# dualHbridge.net
KiCad netlist of a schematic drawn in EAGLE
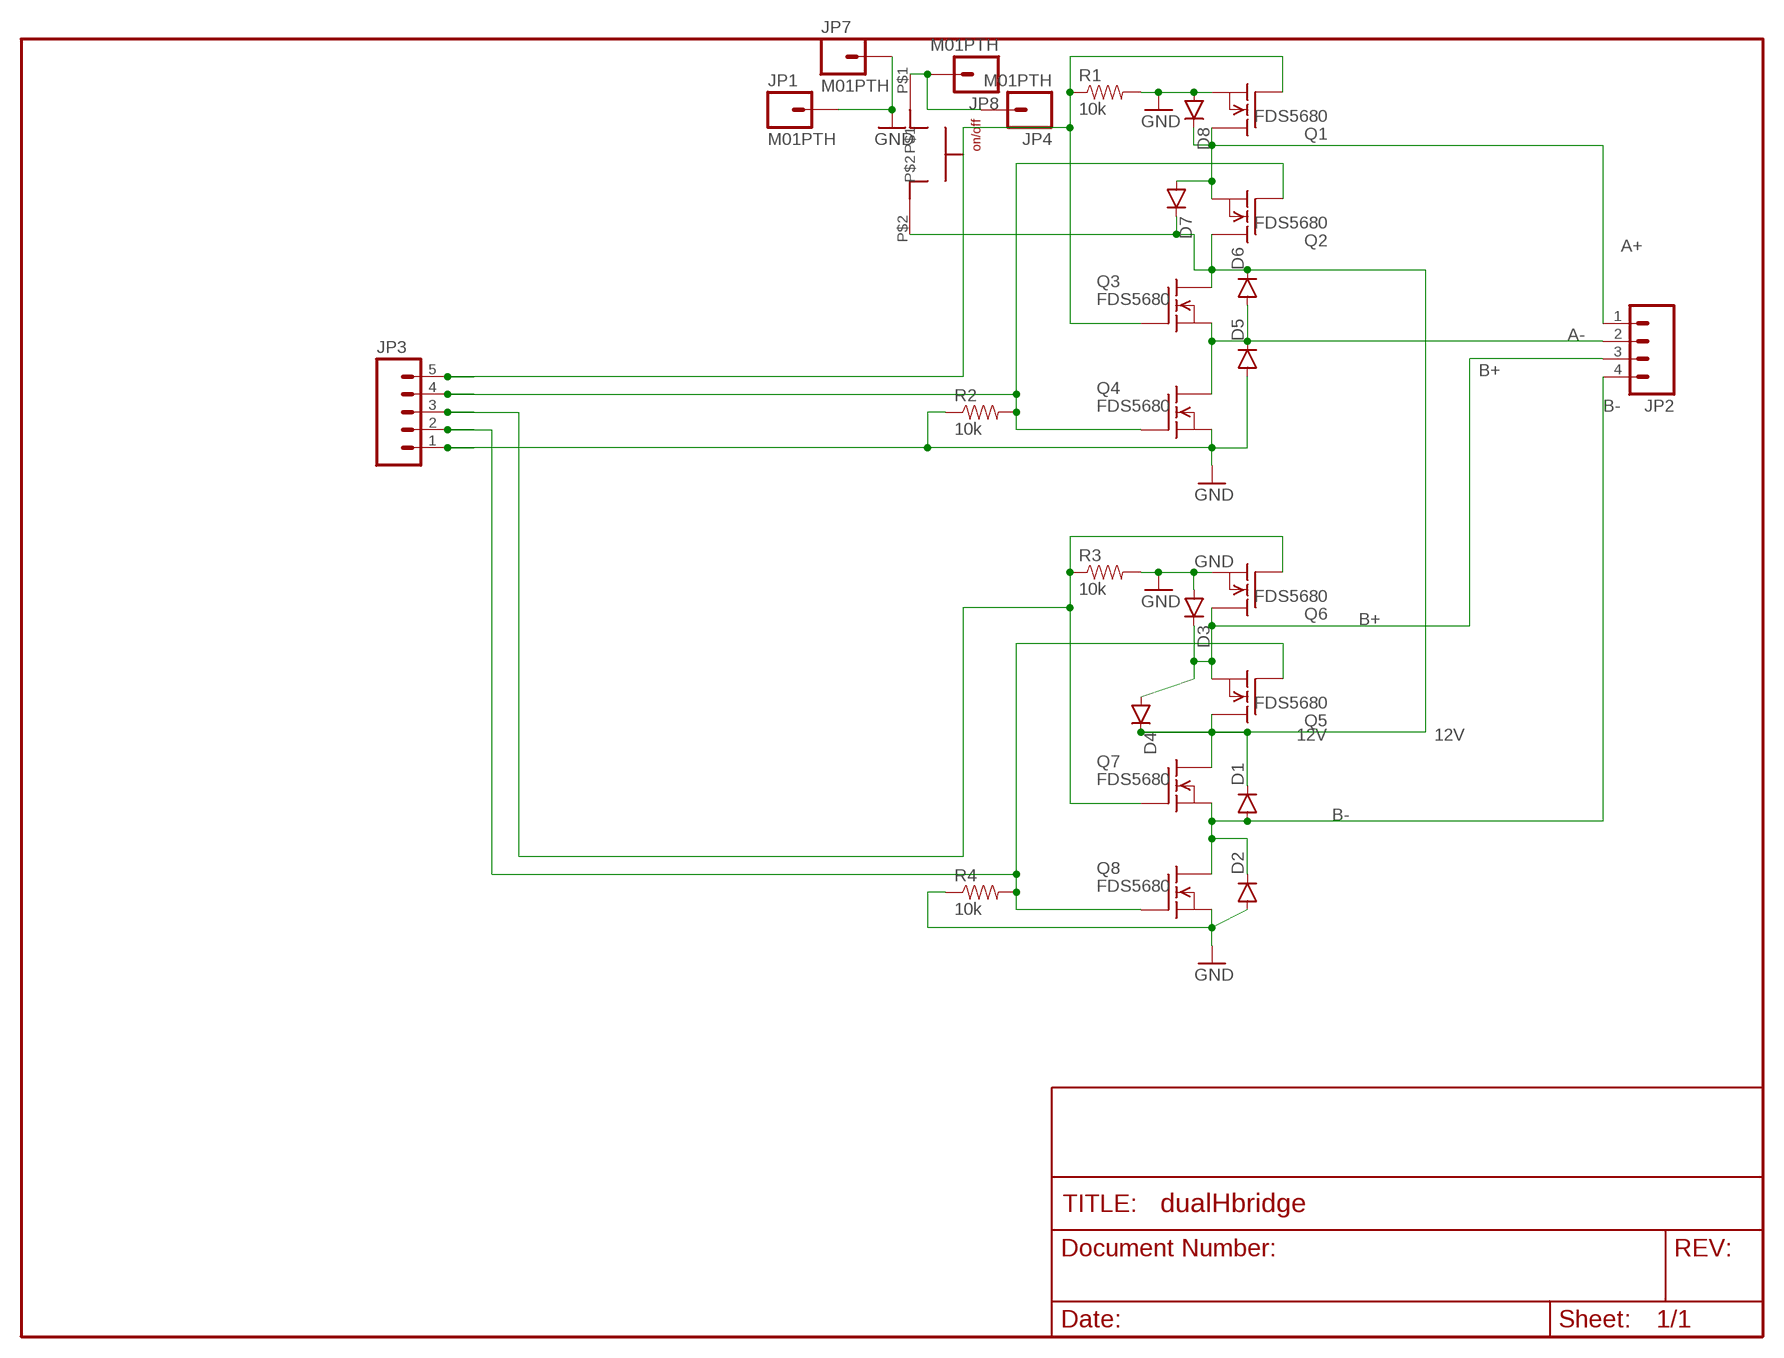
[diagram p0: schematic, sheet 1]

(export (version "E")
  (design (tool "Eeschema 10.0.6"))
  (components
    (comp (ref "D1")
      (value "DIODEKIT2")
      (footprint "eagle-import:DIODE-1N4001-KIT")
      (libsource (lib "eagle-import") (part "DIODEKIT2"))
    )
    (comp (ref "D2")
      (value "DIODEKIT2")
      (footprint "eagle-import:DIODE-1N4001-KIT")
      (libsource (lib "eagle-import") (part "DIODEKIT2"))
    )
    (comp (ref "D3")
      (value "DIODEKIT2")
      (footprint "eagle-import:DIODE-1N4001-KIT")
      (libsource (lib "eagle-import") (part "DIODEKIT2"))
    )
    (comp (ref "D4")
      (value "DIODEKIT2")
      (footprint "eagle-import:DIODE-1N4001-KIT")
      (libsource (lib "eagle-import") (part "DIODEKIT2"))
    )
    (comp (ref "D5")
      (value "DIODEKIT2")
      (footprint "eagle-import:DIODE-1N4001-KIT")
      (libsource (lib "eagle-import") (part "DIODEKIT2"))
    )
    (comp (ref "D6")
      (value "DIODEKIT2")
      (footprint "eagle-import:DIODE-1N4001-KIT")
      (libsource (lib "eagle-import") (part "DIODEKIT2"))
    )
    (comp (ref "D7")
      (value "DIODEKIT2")
      (footprint "eagle-import:DIODE-1N4001-KIT")
      (libsource (lib "eagle-import") (part "DIODEKIT2"))
    )
    (comp (ref "D8")
      (value "DIODEKIT2")
      (footprint "eagle-import:DIODE-1N4001-KIT")
      (libsource (lib "eagle-import") (part "DIODEKIT2"))
    )
    (comp (ref "JP1")
      (value "M01PTH")
      (footprint "eagle-import:1X01")
      (libsource (lib "eagle-import") (part "M01PTH"))
    )
    (comp (ref "JP2")
      (value "M04LONGPADS")
      (footprint "eagle-import:1X04_LONGPADS")
      (libsource (lib "eagle-import") (part "M04LONGPADS"))
    )
    (comp (ref "JP3")
      (value "M05PTH")
      (footprint "eagle-import:1X05")
      (libsource (lib "eagle-import") (part "M05PTH"))
    )
    (comp (ref "JP4")
      (value "M01PTH")
      (footprint "eagle-import:1X01")
      (libsource (lib "eagle-import") (part "M01PTH"))
    )
    (comp (ref "JP7")
      (value "M01PTH")
      (footprint "eagle-import:1X01")
      (libsource (lib "eagle-import") (part "M01PTH"))
    )
    (comp (ref "JP8")
      (value "M01PTH")
      (footprint "eagle-import:1X01")
      (libsource (lib "eagle-import") (part "M01PTH"))
    )
    (comp (ref "Q1")
      (value "FDS5680")
      (footprint "eagle-import:SO-8")
      (libsource (lib "eagle-import") (part "FDS5680"))
    )
    (comp (ref "Q2")
      (value "FDS5680")
      (footprint "eagle-import:SO-8")
      (libsource (lib "eagle-import") (part "FDS5680"))
    )
    (comp (ref "Q3")
      (value "FDS5680")
      (footprint "eagle-import:SO-8")
      (libsource (lib "eagle-import") (part "FDS5680"))
    )
    (comp (ref "Q4")
      (value "FDS5680")
      (footprint "eagle-import:SO-8")
      (libsource (lib "eagle-import") (part "FDS5680"))
    )
    (comp (ref "Q5")
      (value "FDS5680")
      (footprint "eagle-import:SO-8")
      (libsource (lib "eagle-import") (part "FDS5680"))
    )
    (comp (ref "Q6")
      (value "FDS5680")
      (footprint "eagle-import:SO-8")
      (libsource (lib "eagle-import") (part "FDS5680"))
    )
    (comp (ref "Q7")
      (value "FDS5680")
      (footprint "eagle-import:SO-8")
      (libsource (lib "eagle-import") (part "FDS5680"))
    )
    (comp (ref "Q8")
      (value "FDS5680")
      (footprint "eagle-import:SO-8")
      (libsource (lib "eagle-import") (part "FDS5680"))
    )
    (comp (ref "R1")
      (value "10k")
      (footprint "eagle-import:0603-RES")
      (libsource (lib "eagle-import") (part "RESISTOR0603-RES"))
    )
    (comp (ref "R2")
      (value "10k")
      (footprint "eagle-import:0603-RES")
      (libsource (lib "eagle-import") (part "RESISTOR0603-RES"))
    )
    (comp (ref "R3")
      (value "10k")
      (footprint "eagle-import:0603-RES")
      (libsource (lib "eagle-import") (part "RESISTOR0603-RES"))
    )
    (comp (ref "R4")
      (value "10k")
      (footprint "eagle-import:0603-RES")
      (libsource (lib "eagle-import") (part "RESISTOR0603-RES"))
    )
    (comp (ref "U$5")
      (value "CW182-ND")
      (footprint "eagle-import:CW182-ND")
      (libsource (lib "eagle-import") (part "CW182-ND"))
    )
  )
  (nets
    (net (code "1") (name "/12V") (class "Default")
      (node (ref "D1") (pin "C") (pinfunction "C_C") (pintype "passive"))
      (node (ref "D4") (pin "C") (pinfunction "C_C") (pintype "passive"))
      (node (ref "D6") (pin "C") (pinfunction "C_C") (pintype "passive"))
      (node (ref "D7") (pin "C") (pinfunction "C_C") (pintype "passive"))
      (node (ref "Q2") (pin "5") (pinfunction "D_5") (pintype "passive"))
      (node (ref "Q2") (pin "6") (pinfunction "D_6") (pintype "passive"))
      (node (ref "Q2") (pin "7") (pinfunction "D_7") (pintype "passive"))
      (node (ref "Q2") (pin "8") (pinfunction "D_8") (pintype "passive"))
      (node (ref "Q3") (pin "5") (pinfunction "D_5") (pintype "passive"))
      (node (ref "Q3") (pin "6") (pinfunction "D_6") (pintype "passive"))
      (node (ref "Q3") (pin "7") (pinfunction "D_7") (pintype "passive"))
      (node (ref "Q3") (pin "8") (pinfunction "D_8") (pintype "passive"))
      (node (ref "Q5") (pin "5") (pinfunction "D_5") (pintype "passive"))
      (node (ref "Q5") (pin "6") (pinfunction "D_6") (pintype "passive"))
      (node (ref "Q5") (pin "7") (pinfunction "D_7") (pintype "passive"))
      (node (ref "Q5") (pin "8") (pinfunction "D_8") (pintype "passive"))
      (node (ref "Q7") (pin "5") (pinfunction "D_5") (pintype "passive"))
      (node (ref "Q7") (pin "6") (pinfunction "D_6") (pintype "passive"))
      (node (ref "Q7") (pin "7") (pinfunction "D_7") (pintype "passive"))
      (node (ref "Q7") (pin "8") (pinfunction "D_8") (pintype "passive"))
      (node (ref "U$5") (pin "P$2") (pinfunction "P$2_P$2") (pintype "bidirectional"))
    )
    (net (code "2") (name "/A+") (class "Default")
      (node (ref "D7") (pin "A") (pinfunction "A_A") (pintype "passive"))
      (node (ref "D8") (pin "C") (pinfunction "C_C") (pintype "passive"))
      (node (ref "JP2") (pin "1") (pinfunction "1_1") (pintype "passive"))
      (node (ref "Q1") (pin "5") (pinfunction "D_5") (pintype "passive"))
      (node (ref "Q1") (pin "6") (pinfunction "D_6") (pintype "passive"))
      (node (ref "Q1") (pin "7") (pinfunction "D_7") (pintype "passive"))
      (node (ref "Q1") (pin "8") (pinfunction "D_8") (pintype "passive"))
      (node (ref "Q2") (pin "1") (pinfunction "S_1") (pintype "passive"))
      (node (ref "Q2") (pin "2") (pinfunction "S_2") (pintype "passive"))
      (node (ref "Q2") (pin "3") (pinfunction "S_3") (pintype "passive"))
    )
    (net (code "3") (name "/A-") (class "Default")
      (node (ref "D5") (pin "C") (pinfunction "C_C") (pintype "passive"))
      (node (ref "D6") (pin "A") (pinfunction "A_A") (pintype "passive"))
      (node (ref "JP2") (pin "2") (pinfunction "2_2") (pintype "passive"))
      (node (ref "Q3") (pin "1") (pinfunction "S_1") (pintype "passive"))
      (node (ref "Q3") (pin "2") (pinfunction "S_2") (pintype "passive"))
      (node (ref "Q3") (pin "3") (pinfunction "S_3") (pintype "passive"))
      (node (ref "Q4") (pin "5") (pinfunction "D_5") (pintype "passive"))
      (node (ref "Q4") (pin "6") (pinfunction "D_6") (pintype "passive"))
      (node (ref "Q4") (pin "7") (pinfunction "D_7") (pintype "passive"))
      (node (ref "Q4") (pin "8") (pinfunction "D_8") (pintype "passive"))
    )
    (net (code "4") (name "/B+") (class "Default")
      (node (ref "D3") (pin "C") (pinfunction "C_C") (pintype "passive"))
      (node (ref "D4") (pin "A") (pinfunction "A_A") (pintype "passive"))
      (node (ref "JP2") (pin "3") (pinfunction "3_3") (pintype "passive"))
      (node (ref "Q5") (pin "1") (pinfunction "S_1") (pintype "passive"))
      (node (ref "Q5") (pin "2") (pinfunction "S_2") (pintype "passive"))
      (node (ref "Q5") (pin "3") (pinfunction "S_3") (pintype "passive"))
      (node (ref "Q6") (pin "5") (pinfunction "D_5") (pintype "passive"))
      (node (ref "Q6") (pin "6") (pinfunction "D_6") (pintype "passive"))
      (node (ref "Q6") (pin "7") (pinfunction "D_7") (pintype "passive"))
      (node (ref "Q6") (pin "8") (pinfunction "D_8") (pintype "passive"))
    )
    (net (code "5") (name "/B-") (class "Default")
      (node (ref "D1") (pin "A") (pinfunction "A_A") (pintype "passive"))
      (node (ref "D2") (pin "C") (pinfunction "C_C") (pintype "passive"))
      (node (ref "JP2") (pin "4") (pinfunction "4_4") (pintype "passive"))
      (node (ref "Q7") (pin "1") (pinfunction "S_1") (pintype "passive"))
      (node (ref "Q7") (pin "2") (pinfunction "S_2") (pintype "passive"))
      (node (ref "Q7") (pin "3") (pinfunction "S_3") (pintype "passive"))
      (node (ref "Q8") (pin "5") (pinfunction "D_5") (pintype "passive"))
      (node (ref "Q8") (pin "6") (pinfunction "D_6") (pintype "passive"))
      (node (ref "Q8") (pin "7") (pinfunction "D_7") (pintype "passive"))
      (node (ref "Q8") (pin "8") (pinfunction "D_8") (pintype "passive"))
    )
    (net (code "6") (name "GND") (class "Default")
      (node (ref "D2") (pin "A") (pinfunction "A_A") (pintype "passive"))
      (node (ref "D3") (pin "A") (pinfunction "A_A") (pintype "passive"))
      (node (ref "D5") (pin "A") (pinfunction "A_A") (pintype "passive"))
      (node (ref "D8") (pin "A") (pinfunction "A_A") (pintype "passive"))
      (node (ref "JP1") (pin "1") (pinfunction "1_1") (pintype "passive"))
      (node (ref "JP3") (pin "1") (pinfunction "1_1") (pintype "passive"))
      (node (ref "JP7") (pin "1") (pinfunction "1_1") (pintype "passive"))
      (node (ref "Q1") (pin "1") (pinfunction "S_1") (pintype "passive"))
      (node (ref "Q1") (pin "2") (pinfunction "S_2") (pintype "passive"))
      (node (ref "Q1") (pin "3") (pinfunction "S_3") (pintype "passive"))
      (node (ref "Q4") (pin "1") (pinfunction "S_1") (pintype "passive"))
      (node (ref "Q4") (pin "2") (pinfunction "S_2") (pintype "passive"))
      (node (ref "Q4") (pin "3") (pinfunction "S_3") (pintype "passive"))
      (node (ref "Q6") (pin "1") (pinfunction "S_1") (pintype "passive"))
      (node (ref "Q6") (pin "2") (pinfunction "S_2") (pintype "passive"))
      (node (ref "Q6") (pin "3") (pinfunction "S_3") (pintype "passive"))
      (node (ref "Q8") (pin "1") (pinfunction "S_1") (pintype "passive"))
      (node (ref "Q8") (pin "2") (pinfunction "S_2") (pintype "passive"))
      (node (ref "Q8") (pin "3") (pinfunction "S_3") (pintype "passive"))
      (node (ref "R1") (pin "2") (pinfunction "2_2") (pintype "passive"))
      (node (ref "R2") (pin "1") (pinfunction "1_1") (pintype "passive"))
      (node (ref "R3") (pin "2") (pinfunction "2_2") (pintype "passive"))
      (node (ref "R4") (pin "1") (pinfunction "1_1") (pintype "passive"))
    )
    (net (code "7") (name "Net-(JP4-Pad1)") (class "Default")
      (node (ref "JP4") (pin "1") (pinfunction "1_1") (pintype "passive"))
      (node (ref "JP8") (pin "1") (pinfunction "1_1") (pintype "passive"))
      (node (ref "U$5") (pin "P$1") (pinfunction "P$1_P$1") (pintype "bidirectional"))
    )
    (net (code "8") (name "Net-(Q1-G)") (class "Default")
      (node (ref "JP3") (pin "5") (pinfunction "5_5") (pintype "passive"))
      (node (ref "Q1") (pin "4") (pinfunction "G_4") (pintype "passive"))
      (node (ref "Q3") (pin "4") (pinfunction "G_4") (pintype "passive"))
      (node (ref "R1") (pin "1") (pinfunction "1_1") (pintype "passive"))
    )
    (net (code "9") (name "Net-(Q2-G)") (class "Default")
      (node (ref "JP3") (pin "4") (pinfunction "4_4") (pintype "passive"))
      (node (ref "Q2") (pin "4") (pinfunction "G_4") (pintype "passive"))
      (node (ref "Q4") (pin "4") (pinfunction "G_4") (pintype "passive"))
      (node (ref "R2") (pin "2") (pinfunction "2_2") (pintype "passive"))
    )
    (net (code "10") (name "Net-(Q5-G)") (class "Default")
      (node (ref "JP3") (pin "2") (pinfunction "2_2") (pintype "passive"))
      (node (ref "Q5") (pin "4") (pinfunction "G_4") (pintype "passive"))
      (node (ref "Q8") (pin "4") (pinfunction "G_4") (pintype "passive"))
      (node (ref "R4") (pin "2") (pinfunction "2_2") (pintype "passive"))
    )
    (net (code "11") (name "Net-(Q6-G)") (class "Default")
      (node (ref "JP3") (pin "3") (pinfunction "3_3") (pintype "passive"))
      (node (ref "Q6") (pin "4") (pinfunction "G_4") (pintype "passive"))
      (node (ref "Q7") (pin "4") (pinfunction "G_4") (pintype "passive"))
      (node (ref "R3") (pin "1") (pinfunction "1_1") (pintype "passive"))
    )
  )
)
